# LPCB225_-_DISCHARGE.net
KiCad netlist of a schematic drawn in Altium Designer
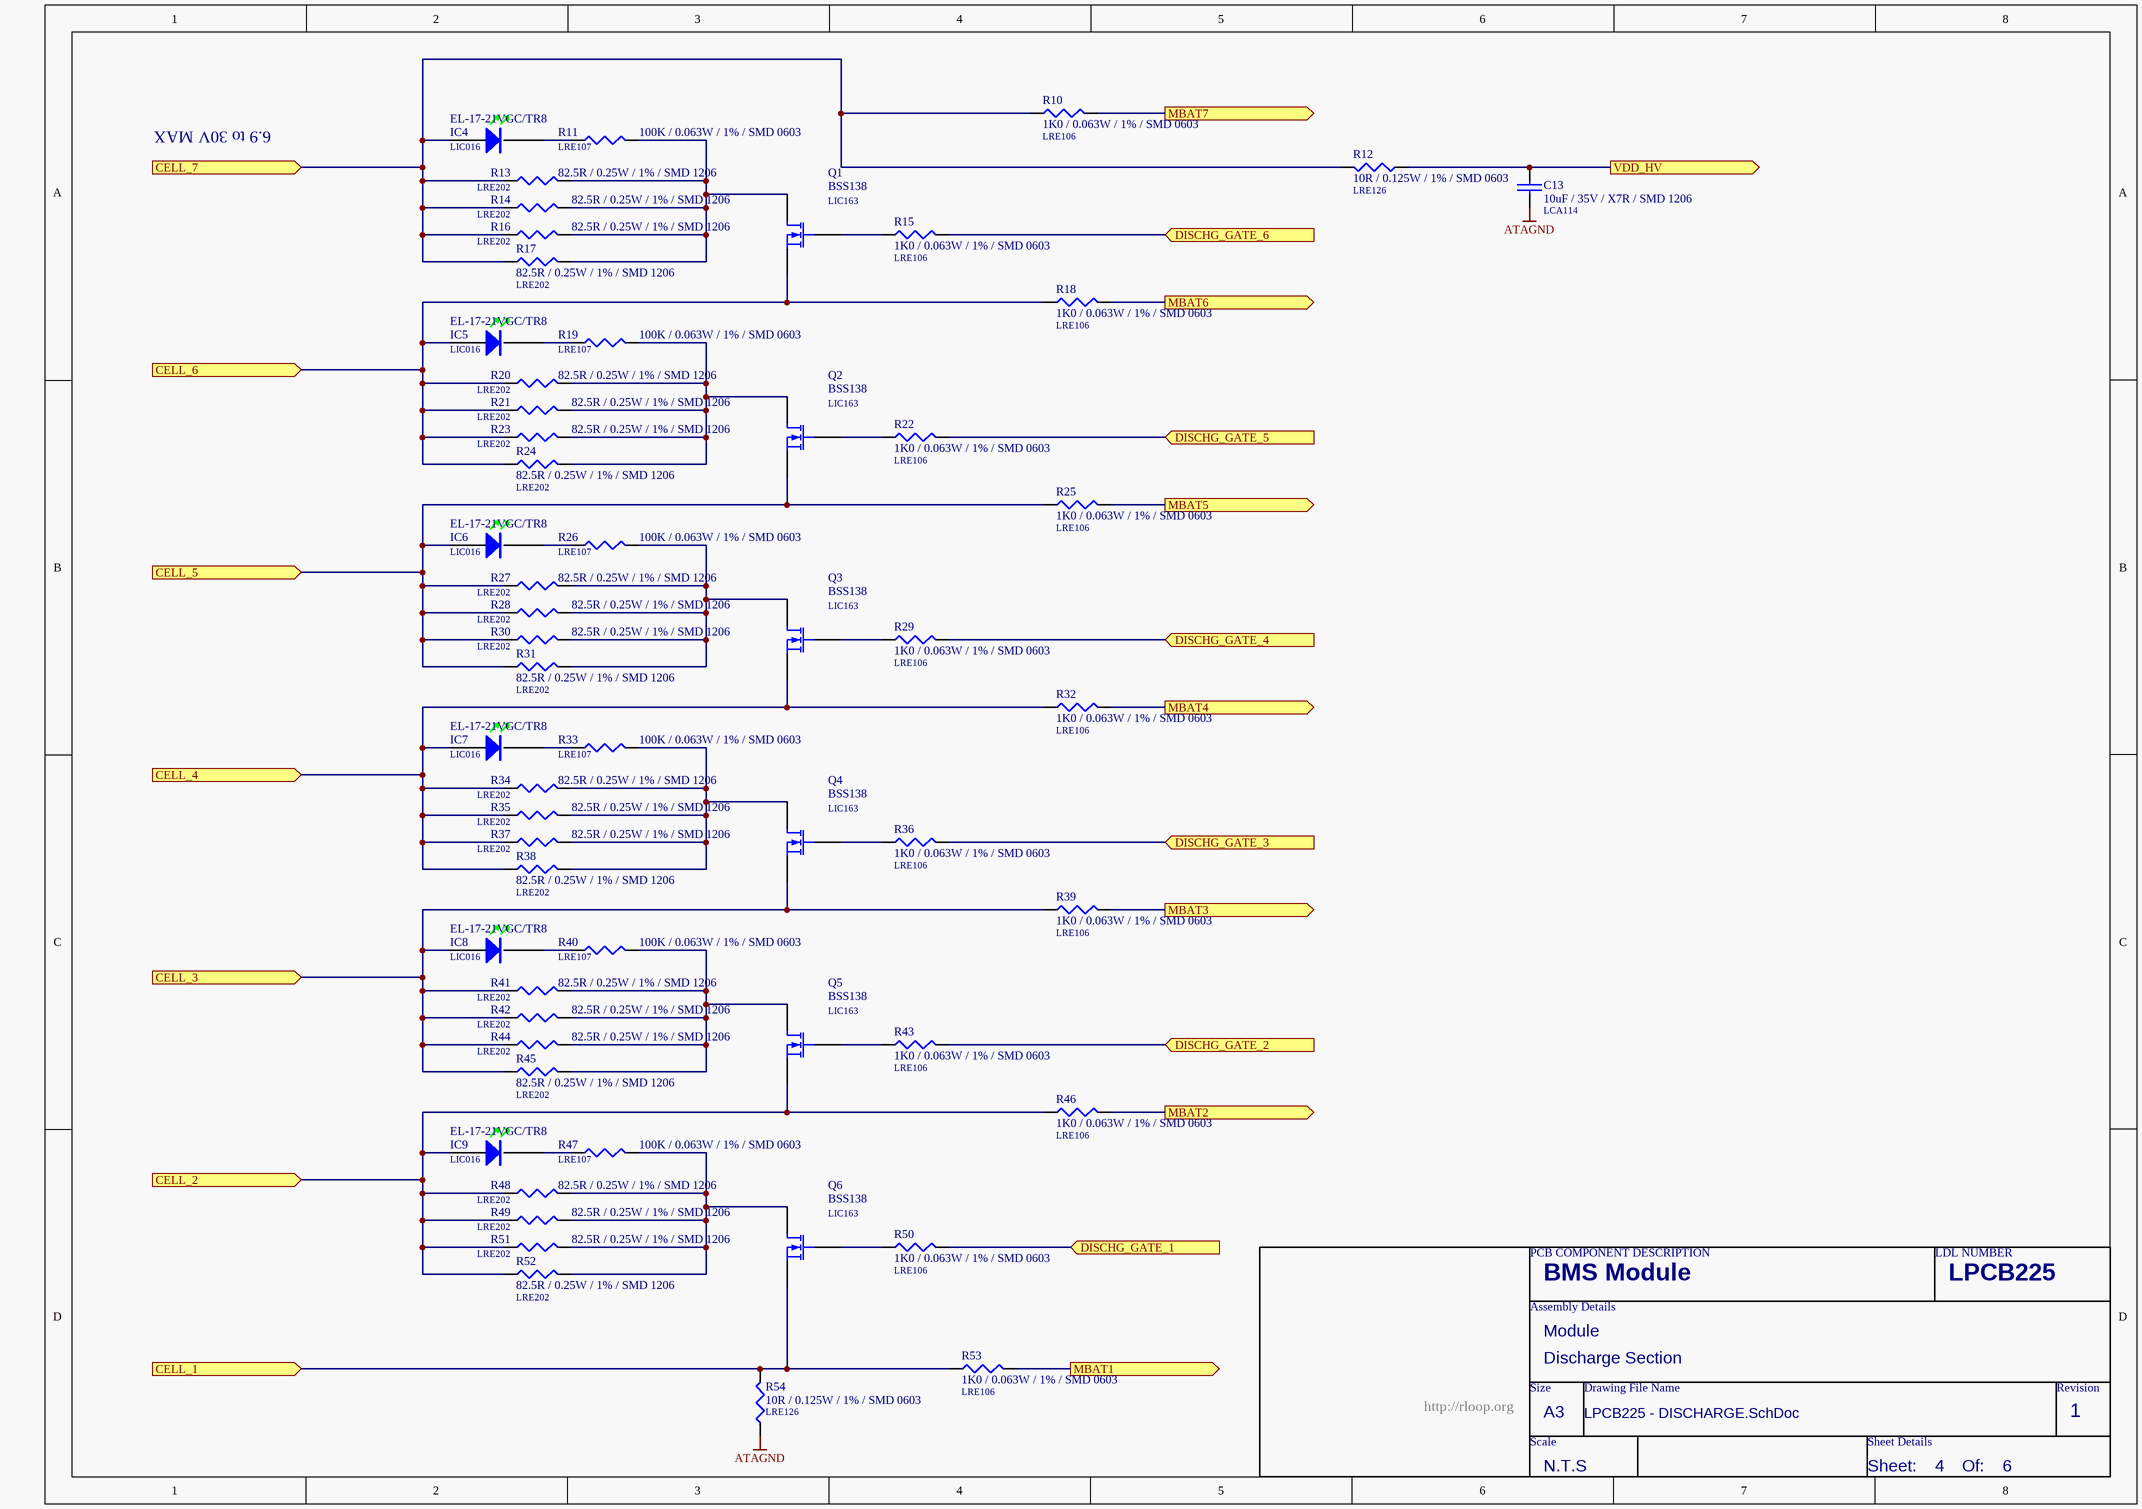
[diagram p0: LPCB225 - DISCHARGE.SchDoc]

(export (version "E")
  (design (tool "Eeschema 10.0.6"))
  (components
    (comp (ref "C13")
      (value "10uF / 35V / X7R / SMD 1206")
      (footprint "LFP043__CC3216-1206")
      (description "Capactor, Ceramic Chip, 10uF, 35V, 20% (X7R), SMD 1206 [LCA114]")
      (fields (field (name "LDL_NUMBER") "LCA114"))
      (libsource (lib "LDL_Capacitors") (part "10uF / 35V / X7R / SMD 1206"))
    )
    (comp (ref "IC4")
      (value "EL-17-21VGC/TR8")
      (footprint "CR2012-0805-LED")
      (description "LED, SMD, 0805 Green [LIC016]")
      (fields (field (name "LDL_NUMBER") "LIC016"))
      (libsource (lib "LDL_Semiconductors") (part "EL-17-21VGC/TR8"))
    )
    (comp (ref "IC5")
      (value "EL-17-21VGC/TR8")
      (footprint "CR2012-0805-LED")
      (description "LED, SMD, 0805 Green [LIC016]")
      (fields (field (name "LDL_NUMBER") "LIC016"))
      (libsource (lib "LDL_Semiconductors") (part "EL-17-21VGC/TR8"))
    )
    (comp (ref "IC6")
      (value "EL-17-21VGC/TR8")
      (footprint "CR2012-0805-LED")
      (description "LED, SMD, 0805 Green [LIC016]")
      (fields (field (name "LDL_NUMBER") "LIC016"))
      (libsource (lib "LDL_Semiconductors") (part "EL-17-21VGC/TR8"))
    )
    (comp (ref "IC7")
      (value "EL-17-21VGC/TR8")
      (footprint "CR2012-0805-LED")
      (description "LED, SMD, 0805 Green [LIC016]")
      (fields (field (name "LDL_NUMBER") "LIC016"))
      (libsource (lib "LDL_Semiconductors") (part "EL-17-21VGC/TR8"))
    )
    (comp (ref "IC8")
      (value "EL-17-21VGC/TR8")
      (footprint "CR2012-0805-LED")
      (description "LED, SMD, 0805 Green [LIC016]")
      (fields (field (name "LDL_NUMBER") "LIC016"))
      (libsource (lib "LDL_Semiconductors") (part "EL-17-21VGC/TR8"))
    )
    (comp (ref "IC9")
      (value "EL-17-21VGC/TR8")
      (footprint "CR2012-0805-LED")
      (description "LED, SMD, 0805 Green [LIC016]")
      (fields (field (name "LDL_NUMBER") "LIC016"))
      (libsource (lib "LDL_Semiconductors") (part "EL-17-21VGC/TR8"))
    )
    (comp (ref "Q1")
      (value "BSS138")
      (footprint "LFP021__SOT23")
      (description "FET, N Channel, Logic Level, SMD SOT23 [LIC163]")
      (fields (field (name "LDL_NUMBER") "LIC163"))
      (libsource (lib "LDL_Semiconductors") (part "BSS138"))
    )
    (comp (ref "Q2")
      (value "BSS138")
      (footprint "LFP021__SOT23")
      (description "FET, N Channel, Logic Level, SMD SOT23 [LIC163]")
      (fields (field (name "LDL_NUMBER") "LIC163"))
      (libsource (lib "LDL_Semiconductors") (part "BSS138"))
    )
    (comp (ref "Q3")
      (value "BSS138")
      (footprint "LFP021__SOT23")
      (description "FET, N Channel, Logic Level, SMD SOT23 [LIC163]")
      (fields (field (name "LDL_NUMBER") "LIC163"))
      (libsource (lib "LDL_Semiconductors") (part "BSS138"))
    )
    (comp (ref "Q4")
      (value "BSS138")
      (footprint "LFP021__SOT23")
      (description "FET, N Channel, Logic Level, SMD SOT23 [LIC163]")
      (fields (field (name "LDL_NUMBER") "LIC163"))
      (libsource (lib "LDL_Semiconductors") (part "BSS138"))
    )
    (comp (ref "Q5")
      (value "BSS138")
      (footprint "LFP021__SOT23")
      (description "FET, N Channel, Logic Level, SMD SOT23 [LIC163]")
      (fields (field (name "LDL_NUMBER") "LIC163"))
      (libsource (lib "LDL_Semiconductors") (part "BSS138"))
    )
    (comp (ref "Q6")
      (value "BSS138")
      (footprint "LFP021__SOT23")
      (description "FET, N Channel, Logic Level, SMD SOT23 [LIC163]")
      (fields (field (name "LDL_NUMBER") "LIC163"))
      (libsource (lib "LDL_Semiconductors") (part "BSS138"))
    )
    (comp (ref "R10")
      (value "1K0 / 0.063W / 1% / SMD 0603")
      (footprint "LFP020__CR1608-0603-IPC7351_B")
      (description "Resistor, Ceramic Chip, 1K0, 0.063W, 1%, SMD 0603 [LRE106]")
      (fields (field (name "LDL_NUMBER") "LRE106"))
      (libsource (lib "LDL_Resistors") (part "1K0 / 0.063W / 1% / SMD 0603"))
    )
    (comp (ref "R11")
      (value "100K / 0.063W / 1% / SMD 0603")
      (footprint "LFP020__CR1608-0603-IPC7351_B")
      (description "Resistor, Ceramic Chip, 100K0, 0.063W, 1%, SMD 0603 [LRE107]")
      (fields (field (name "LDL_NUMBER") "LRE107"))
      (libsource (lib "LDL_Resistors") (part "100K / 0.063W / 1% / SMD 0603"))
    )
    (comp (ref "R12")
      (value "10R / 0.125W / 1% / SMD 0603")
      (footprint "LFP020__CR1608-0603-IPC7351_B")
      (description "Resistor, Ceramic Chip, 10R, 0.063W, 1%, SMD 0603 [LRE126]")
      (fields (field (name "LDL_NUMBER") "LRE126"))
      (libsource (lib "LDL_Resistors") (part "10R / 0.125W / 1% / SMD 0603"))
    )
    (comp (ref "R13")
      (value "82.5R / 0.25W / 1% / SMD 1206")
      (footprint "LFP107__CR3216-1206")
      (description "Resistor, Ceramic Chip, 82.5R, 0.25W, 1%, SMD 1206 [LRE202]")
      (fields (field (name "LDL_NUMBER") "LRE202"))
      (libsource (lib "LDL_Resistors") (part "82.5R / 0.25W / 1% / SMD 1206"))
    )
    (comp (ref "R14")
      (value "82.5R / 0.25W / 1% / SMD 1206")
      (footprint "LFP107__CR3216-1206")
      (description "Resistor, Ceramic Chip, 82.5R, 0.25W, 1%, SMD 1206 [LRE202]")
      (fields (field (name "LDL_NUMBER") "LRE202"))
      (libsource (lib "LDL_Resistors") (part "82.5R / 0.25W / 1% / SMD 1206"))
    )
    (comp (ref "R15")
      (value "1K0 / 0.063W / 1% / SMD 0603")
      (footprint "LFP020__CR1608-0603-IPC7351_B")
      (description "Resistor, Ceramic Chip, 1K0, 0.063W, 1%, SMD 0603 [LRE106]")
      (fields (field (name "LDL_NUMBER") "LRE106"))
      (libsource (lib "LDL_Resistors") (part "1K0 / 0.063W / 1% / SMD 0603"))
    )
    (comp (ref "R16")
      (value "82.5R / 0.25W / 1% / SMD 1206")
      (footprint "LFP107__CR3216-1206")
      (description "Resistor, Ceramic Chip, 82.5R, 0.25W, 1%, SMD 1206 [LRE202]")
      (fields (field (name "LDL_NUMBER") "LRE202"))
      (libsource (lib "LDL_Resistors") (part "82.5R / 0.25W / 1% / SMD 1206"))
    )
    (comp (ref "R17")
      (value "82.5R / 0.25W / 1% / SMD 1206")
      (footprint "LFP107__CR3216-1206")
      (description "Resistor, Ceramic Chip, 82.5R, 0.25W, 1%, SMD 1206 [LRE202]")
      (fields (field (name "LDL_NUMBER") "LRE202"))
      (libsource (lib "LDL_Resistors") (part "82.5R / 0.25W / 1% / SMD 1206"))
    )
    (comp (ref "R18")
      (value "1K0 / 0.063W / 1% / SMD 0603")
      (footprint "LFP020__CR1608-0603-IPC7351_B")
      (description "Resistor, Ceramic Chip, 1K0, 0.063W, 1%, SMD 0603 [LRE106]")
      (fields (field (name "LDL_NUMBER") "LRE106"))
      (libsource (lib "LDL_Resistors") (part "1K0 / 0.063W / 1% / SMD 0603"))
    )
    (comp (ref "R19")
      (value "100K / 0.063W / 1% / SMD 0603")
      (footprint "LFP020__CR1608-0603-IPC7351_B")
      (description "Resistor, Ceramic Chip, 100K0, 0.063W, 1%, SMD 0603 [LRE107]")
      (fields (field (name "LDL_NUMBER") "LRE107"))
      (libsource (lib "LDL_Resistors") (part "100K / 0.063W / 1% / SMD 0603"))
    )
    (comp (ref "R20")
      (value "82.5R / 0.25W / 1% / SMD 1206")
      (footprint "LFP107__CR3216-1206")
      (description "Resistor, Ceramic Chip, 82.5R, 0.25W, 1%, SMD 1206 [LRE202]")
      (fields (field (name "LDL_NUMBER") "LRE202"))
      (libsource (lib "LDL_Resistors") (part "82.5R / 0.25W / 1% / SMD 1206"))
    )
    (comp (ref "R21")
      (value "82.5R / 0.25W / 1% / SMD 1206")
      (footprint "LFP107__CR3216-1206")
      (description "Resistor, Ceramic Chip, 82.5R, 0.25W, 1%, SMD 1206 [LRE202]")
      (fields (field (name "LDL_NUMBER") "LRE202"))
      (libsource (lib "LDL_Resistors") (part "82.5R / 0.25W / 1% / SMD 1206"))
    )
    (comp (ref "R22")
      (value "1K0 / 0.063W / 1% / SMD 0603")
      (footprint "LFP020__CR1608-0603-IPC7351_B")
      (description "Resistor, Ceramic Chip, 1K0, 0.063W, 1%, SMD 0603 [LRE106]")
      (fields (field (name "LDL_NUMBER") "LRE106"))
      (libsource (lib "LDL_Resistors") (part "1K0 / 0.063W / 1% / SMD 0603"))
    )
    (comp (ref "R23")
      (value "82.5R / 0.25W / 1% / SMD 1206")
      (footprint "LFP107__CR3216-1206")
      (description "Resistor, Ceramic Chip, 82.5R, 0.25W, 1%, SMD 1206 [LRE202]")
      (fields (field (name "LDL_NUMBER") "LRE202"))
      (libsource (lib "LDL_Resistors") (part "82.5R / 0.25W / 1% / SMD 1206"))
    )
    (comp (ref "R24")
      (value "82.5R / 0.25W / 1% / SMD 1206")
      (footprint "LFP107__CR3216-1206")
      (description "Resistor, Ceramic Chip, 82.5R, 0.25W, 1%, SMD 1206 [LRE202]")
      (fields (field (name "LDL_NUMBER") "LRE202"))
      (libsource (lib "LDL_Resistors") (part "82.5R / 0.25W / 1% / SMD 1206"))
    )
    (comp (ref "R25")
      (value "1K0 / 0.063W / 1% / SMD 0603")
      (footprint "LFP020__CR1608-0603-IPC7351_B")
      (description "Resistor, Ceramic Chip, 1K0, 0.063W, 1%, SMD 0603 [LRE106]")
      (fields (field (name "LDL_NUMBER") "LRE106"))
      (libsource (lib "LDL_Resistors") (part "1K0 / 0.063W / 1% / SMD 0603"))
    )
    (comp (ref "R26")
      (value "100K / 0.063W / 1% / SMD 0603")
      (footprint "LFP020__CR1608-0603-IPC7351_B")
      (description "Resistor, Ceramic Chip, 100K0, 0.063W, 1%, SMD 0603 [LRE107]")
      (fields (field (name "LDL_NUMBER") "LRE107"))
      (libsource (lib "LDL_Resistors") (part "100K / 0.063W / 1% / SMD 0603"))
    )
    (comp (ref "R27")
      (value "82.5R / 0.25W / 1% / SMD 1206")
      (footprint "LFP107__CR3216-1206")
      (description "Resistor, Ceramic Chip, 82.5R, 0.25W, 1%, SMD 1206 [LRE202]")
      (fields (field (name "LDL_NUMBER") "LRE202"))
      (libsource (lib "LDL_Resistors") (part "82.5R / 0.25W / 1% / SMD 1206"))
    )
    (comp (ref "R28")
      (value "82.5R / 0.25W / 1% / SMD 1206")
      (footprint "LFP107__CR3216-1206")
      (description "Resistor, Ceramic Chip, 82.5R, 0.25W, 1%, SMD 1206 [LRE202]")
      (fields (field (name "LDL_NUMBER") "LRE202"))
      (libsource (lib "LDL_Resistors") (part "82.5R / 0.25W / 1% / SMD 1206"))
    )
    (comp (ref "R29")
      (value "1K0 / 0.063W / 1% / SMD 0603")
      (footprint "LFP020__CR1608-0603-IPC7351_B")
      (description "Resistor, Ceramic Chip, 1K0, 0.063W, 1%, SMD 0603 [LRE106]")
      (fields (field (name "LDL_NUMBER") "LRE106"))
      (libsource (lib "LDL_Resistors") (part "1K0 / 0.063W / 1% / SMD 0603"))
    )
    (comp (ref "R30")
      (value "82.5R / 0.25W / 1% / SMD 1206")
      (footprint "LFP107__CR3216-1206")
      (description "Resistor, Ceramic Chip, 82.5R, 0.25W, 1%, SMD 1206 [LRE202]")
      (fields (field (name "LDL_NUMBER") "LRE202"))
      (libsource (lib "LDL_Resistors") (part "82.5R / 0.25W / 1% / SMD 1206"))
    )
    (comp (ref "R31")
      (value "82.5R / 0.25W / 1% / SMD 1206")
      (footprint "LFP107__CR3216-1206")
      (description "Resistor, Ceramic Chip, 82.5R, 0.25W, 1%, SMD 1206 [LRE202]")
      (fields (field (name "LDL_NUMBER") "LRE202"))
      (libsource (lib "LDL_Resistors") (part "82.5R / 0.25W / 1% / SMD 1206"))
    )
    (comp (ref "R32")
      (value "1K0 / 0.063W / 1% / SMD 0603")
      (footprint "LFP020__CR1608-0603-IPC7351_B")
      (description "Resistor, Ceramic Chip, 1K0, 0.063W, 1%, SMD 0603 [LRE106]")
      (fields (field (name "LDL_NUMBER") "LRE106"))
      (libsource (lib "LDL_Resistors") (part "1K0 / 0.063W / 1% / SMD 0603"))
    )
    (comp (ref "R33")
      (value "100K / 0.063W / 1% / SMD 0603")
      (footprint "LFP020__CR1608-0603-IPC7351_B")
      (description "Resistor, Ceramic Chip, 100K0, 0.063W, 1%, SMD 0603 [LRE107]")
      (fields (field (name "LDL_NUMBER") "LRE107"))
      (libsource (lib "LDL_Resistors") (part "100K / 0.063W / 1% / SMD 0603"))
    )
    (comp (ref "R34")
      (value "82.5R / 0.25W / 1% / SMD 1206")
      (footprint "LFP107__CR3216-1206")
      (description "Resistor, Ceramic Chip, 82.5R, 0.25W, 1%, SMD 1206 [LRE202]")
      (fields (field (name "LDL_NUMBER") "LRE202"))
      (libsource (lib "LDL_Resistors") (part "82.5R / 0.25W / 1% / SMD 1206"))
    )
    (comp (ref "R35")
      (value "82.5R / 0.25W / 1% / SMD 1206")
      (footprint "LFP107__CR3216-1206")
      (description "Resistor, Ceramic Chip, 82.5R, 0.25W, 1%, SMD 1206 [LRE202]")
      (fields (field (name "LDL_NUMBER") "LRE202"))
      (libsource (lib "LDL_Resistors") (part "82.5R / 0.25W / 1% / SMD 1206"))
    )
    (comp (ref "R36")
      (value "1K0 / 0.063W / 1% / SMD 0603")
      (footprint "LFP020__CR1608-0603-IPC7351_B")
      (description "Resistor, Ceramic Chip, 1K0, 0.063W, 1%, SMD 0603 [LRE106]")
      (fields (field (name "LDL_NUMBER") "LRE106"))
      (libsource (lib "LDL_Resistors") (part "1K0 / 0.063W / 1% / SMD 0603"))
    )
    (comp (ref "R37")
      (value "82.5R / 0.25W / 1% / SMD 1206")
      (footprint "LFP107__CR3216-1206")
      (description "Resistor, Ceramic Chip, 82.5R, 0.25W, 1%, SMD 1206 [LRE202]")
      (fields (field (name "LDL_NUMBER") "LRE202"))
      (libsource (lib "LDL_Resistors") (part "82.5R / 0.25W / 1% / SMD 1206"))
    )
    (comp (ref "R38")
      (value "82.5R / 0.25W / 1% / SMD 1206")
      (footprint "LFP107__CR3216-1206")
      (description "Resistor, Ceramic Chip, 82.5R, 0.25W, 1%, SMD 1206 [LRE202]")
      (fields (field (name "LDL_NUMBER") "LRE202"))
      (libsource (lib "LDL_Resistors") (part "82.5R / 0.25W / 1% / SMD 1206"))
    )
    (comp (ref "R39")
      (value "1K0 / 0.063W / 1% / SMD 0603")
      (footprint "LFP020__CR1608-0603-IPC7351_B")
      (description "Resistor, Ceramic Chip, 1K0, 0.063W, 1%, SMD 0603 [LRE106]")
      (fields (field (name "LDL_NUMBER") "LRE106"))
      (libsource (lib "LDL_Resistors") (part "1K0 / 0.063W / 1% / SMD 0603"))
    )
    (comp (ref "R40")
      (value "100K / 0.063W / 1% / SMD 0603")
      (footprint "LFP020__CR1608-0603-IPC7351_B")
      (description "Resistor, Ceramic Chip, 100K0, 0.063W, 1%, SMD 0603 [LRE107]")
      (fields (field (name "LDL_NUMBER") "LRE107"))
      (libsource (lib "LDL_Resistors") (part "100K / 0.063W / 1% / SMD 0603"))
    )
    (comp (ref "R41")
      (value "82.5R / 0.25W / 1% / SMD 1206")
      (footprint "LFP107__CR3216-1206")
      (description "Resistor, Ceramic Chip, 82.5R, 0.25W, 1%, SMD 1206 [LRE202]")
      (fields (field (name "LDL_NUMBER") "LRE202"))
      (libsource (lib "LDL_Resistors") (part "82.5R / 0.25W / 1% / SMD 1206"))
    )
    (comp (ref "R42")
      (value "82.5R / 0.25W / 1% / SMD 1206")
      (footprint "LFP107__CR3216-1206")
      (description "Resistor, Ceramic Chip, 82.5R, 0.25W, 1%, SMD 1206 [LRE202]")
      (fields (field (name "LDL_NUMBER") "LRE202"))
      (libsource (lib "LDL_Resistors") (part "82.5R / 0.25W / 1% / SMD 1206"))
    )
    (comp (ref "R43")
      (value "1K0 / 0.063W / 1% / SMD 0603")
      (footprint "LFP020__CR1608-0603-IPC7351_B")
      (description "Resistor, Ceramic Chip, 1K0, 0.063W, 1%, SMD 0603 [LRE106]")
      (fields (field (name "LDL_NUMBER") "LRE106"))
      (libsource (lib "LDL_Resistors") (part "1K0 / 0.063W / 1% / SMD 0603"))
    )
    (comp (ref "R44")
      (value "82.5R / 0.25W / 1% / SMD 1206")
      (footprint "LFP107__CR3216-1206")
      (description "Resistor, Ceramic Chip, 82.5R, 0.25W, 1%, SMD 1206 [LRE202]")
      (fields (field (name "LDL_NUMBER") "LRE202"))
      (libsource (lib "LDL_Resistors") (part "82.5R / 0.25W / 1% / SMD 1206"))
    )
    (comp (ref "R45")
      (value "82.5R / 0.25W / 1% / SMD 1206")
      (footprint "LFP107__CR3216-1206")
      (description "Resistor, Ceramic Chip, 82.5R, 0.25W, 1%, SMD 1206 [LRE202]")
      (fields (field (name "LDL_NUMBER") "LRE202"))
      (libsource (lib "LDL_Resistors") (part "82.5R / 0.25W / 1% / SMD 1206"))
    )
    (comp (ref "R46")
      (value "1K0 / 0.063W / 1% / SMD 0603")
      (footprint "LFP020__CR1608-0603-IPC7351_B")
      (description "Resistor, Ceramic Chip, 1K0, 0.063W, 1%, SMD 0603 [LRE106]")
      (fields (field (name "LDL_NUMBER") "LRE106"))
      (libsource (lib "LDL_Resistors") (part "1K0 / 0.063W / 1% / SMD 0603"))
    )
    (comp (ref "R47")
      (value "100K / 0.063W / 1% / SMD 0603")
      (footprint "LFP020__CR1608-0603-IPC7351_B")
      (description "Resistor, Ceramic Chip, 100K0, 0.063W, 1%, SMD 0603 [LRE107]")
      (fields (field (name "LDL_NUMBER") "LRE107"))
      (libsource (lib "LDL_Resistors") (part "100K / 0.063W / 1% / SMD 0603"))
    )
    (comp (ref "R48")
      (value "82.5R / 0.25W / 1% / SMD 1206")
      (footprint "LFP107__CR3216-1206")
      (description "Resistor, Ceramic Chip, 82.5R, 0.25W, 1%, SMD 1206 [LRE202]")
      (fields (field (name "LDL_NUMBER") "LRE202"))
      (libsource (lib "LDL_Resistors") (part "82.5R / 0.25W / 1% / SMD 1206"))
    )
    (comp (ref "R49")
      (value "82.5R / 0.25W / 1% / SMD 1206")
      (footprint "LFP107__CR3216-1206")
      (description "Resistor, Ceramic Chip, 82.5R, 0.25W, 1%, SMD 1206 [LRE202]")
      (fields (field (name "LDL_NUMBER") "LRE202"))
      (libsource (lib "LDL_Resistors") (part "82.5R / 0.25W / 1% / SMD 1206"))
    )
    (comp (ref "R50")
      (value "1K0 / 0.063W / 1% / SMD 0603")
      (footprint "LFP020__CR1608-0603-IPC7351_B")
      (description "Resistor, Ceramic Chip, 1K0, 0.063W, 1%, SMD 0603 [LRE106]")
      (fields (field (name "LDL_NUMBER") "LRE106"))
      (libsource (lib "LDL_Resistors") (part "1K0 / 0.063W / 1% / SMD 0603"))
    )
    (comp (ref "R51")
      (value "82.5R / 0.25W / 1% / SMD 1206")
      (footprint "LFP107__CR3216-1206")
      (description "Resistor, Ceramic Chip, 82.5R, 0.25W, 1%, SMD 1206 [LRE202]")
      (fields (field (name "LDL_NUMBER") "LRE202"))
      (libsource (lib "LDL_Resistors") (part "82.5R / 0.25W / 1% / SMD 1206"))
    )
    (comp (ref "R52")
      (value "82.5R / 0.25W / 1% / SMD 1206")
      (footprint "LFP107__CR3216-1206")
      (description "Resistor, Ceramic Chip, 82.5R, 0.25W, 1%, SMD 1206 [LRE202]")
      (fields (field (name "LDL_NUMBER") "LRE202"))
      (libsource (lib "LDL_Resistors") (part "82.5R / 0.25W / 1% / SMD 1206"))
    )
    (comp (ref "R53")
      (value "1K0 / 0.063W / 1% / SMD 0603")
      (footprint "LFP020__CR1608-0603-IPC7351_B")
      (description "Resistor, Ceramic Chip, 1K0, 0.063W, 1%, SMD 0603 [LRE106]")
      (fields (field (name "LDL_NUMBER") "LRE106"))
      (libsource (lib "LDL_Resistors") (part "1K0 / 0.063W / 1% / SMD 0603"))
    )
    (comp (ref "R54")
      (value "10R / 0.125W / 1% / SMD 0603")
      (footprint "LFP020__CR1608-0603-IPC7351_B")
      (description "Resistor, Ceramic Chip, 10R, 0.063W, 1%, SMD 0603 [LRE126]")
      (fields (field (name "LDL_NUMBER") "LRE126"))
      (libsource (lib "LDL_Resistors") (part "10R / 0.125W / 1% / SMD 0603"))
    )
  )
  (nets
    (net (code "1") (name "/CELL_1") (class "Default")
      (node (ref "Q6") (pin "2") (pinfunction "S_2") (pintype "passive"))
      (node (ref "R53") (pin "1") (pintype "passive"))
      (node (ref "R54") (pin "2") (pintype "passive"))
    )
    (net (code "2") (name "/CELL_2") (class "Default")
      (node (ref "IC9") (pin "A") (pintype "passive"))
      (node (ref "Q5") (pin "2") (pinfunction "S_2") (pintype "passive"))
      (node (ref "R46") (pin "1") (pintype "passive"))
      (node (ref "R48") (pin "1") (pintype "passive"))
      (node (ref "R49") (pin "1") (pintype "passive"))
      (node (ref "R51") (pin "1") (pintype "passive"))
      (node (ref "R52") (pin "1") (pintype "passive"))
    )
    (net (code "3") (name "/CELL_3") (class "Default")
      (node (ref "IC8") (pin "A") (pintype "passive"))
      (node (ref "Q4") (pin "2") (pinfunction "S_2") (pintype "passive"))
      (node (ref "R39") (pin "1") (pintype "passive"))
      (node (ref "R41") (pin "1") (pintype "passive"))
      (node (ref "R42") (pin "1") (pintype "passive"))
      (node (ref "R44") (pin "1") (pintype "passive"))
      (node (ref "R45") (pin "1") (pintype "passive"))
    )
    (net (code "4") (name "/CELL_4") (class "Default")
      (node (ref "IC7") (pin "A") (pintype "passive"))
      (node (ref "Q3") (pin "2") (pinfunction "S_2") (pintype "passive"))
      (node (ref "R32") (pin "1") (pintype "passive"))
      (node (ref "R34") (pin "1") (pintype "passive"))
      (node (ref "R35") (pin "1") (pintype "passive"))
      (node (ref "R37") (pin "1") (pintype "passive"))
      (node (ref "R38") (pin "1") (pintype "passive"))
    )
    (net (code "5") (name "/CELL_5") (class "Default")
      (node (ref "IC6") (pin "A") (pintype "passive"))
      (node (ref "Q2") (pin "2") (pinfunction "S_2") (pintype "passive"))
      (node (ref "R25") (pin "1") (pintype "passive"))
      (node (ref "R27") (pin "1") (pintype "passive"))
      (node (ref "R28") (pin "1") (pintype "passive"))
      (node (ref "R30") (pin "1") (pintype "passive"))
      (node (ref "R31") (pin "1") (pintype "passive"))
    )
    (net (code "6") (name "/CELL_6") (class "Default")
      (node (ref "IC5") (pin "A") (pintype "passive"))
      (node (ref "Q1") (pin "2") (pinfunction "S_2") (pintype "passive"))
      (node (ref "R18") (pin "1") (pintype "passive"))
      (node (ref "R20") (pin "1") (pintype "passive"))
      (node (ref "R21") (pin "1") (pintype "passive"))
      (node (ref "R23") (pin "1") (pintype "passive"))
      (node (ref "R24") (pin "1") (pintype "passive"))
    )
    (net (code "7") (name "/CELL_7") (class "Default")
      (node (ref "IC4") (pin "A") (pintype "passive"))
      (node (ref "R10") (pin "1") (pintype "passive"))
      (node (ref "R12") (pin "2") (pintype "passive"))
      (node (ref "R13") (pin "1") (pintype "passive"))
      (node (ref "R14") (pin "1") (pintype "passive"))
      (node (ref "R16") (pin "1") (pintype "passive"))
      (node (ref "R17") (pin "1") (pintype "passive"))
    )
    (net (code "8") (name "/DISCHG_GATE_1") (class "Default")
      (node (ref "R50") (pin "2") (pintype "passive"))
    )
    (net (code "9") (name "/DISCHG_GATE_2") (class "Default")
      (node (ref "R43") (pin "2") (pintype "passive"))
    )
    (net (code "10") (name "/DISCHG_GATE_3") (class "Default")
      (node (ref "R36") (pin "2") (pintype "passive"))
    )
    (net (code "11") (name "/DISCHG_GATE_4") (class "Default")
      (node (ref "R29") (pin "2") (pintype "passive"))
    )
    (net (code "12") (name "/DISCHG_GATE_5") (class "Default")
      (node (ref "R22") (pin "2") (pintype "passive"))
    )
    (net (code "13") (name "/DISCHG_GATE_6") (class "Default")
      (node (ref "R15") (pin "2") (pintype "passive"))
    )
    (net (code "14") (name "/MBAT1") (class "Default") (node (ref "R53") (pin "2") (pintype "passive")))
    (net (code "15") (name "/MBAT2") (class "Default") (node (ref "R46") (pin "2") (pintype "passive")))
    (net (code "16") (name "/MBAT3") (class "Default") (node (ref "R39") (pin "2") (pintype "passive")))
    (net (code "17") (name "/MBAT4") (class "Default") (node (ref "R32") (pin "2") (pintype "passive")))
    (net (code "18") (name "/MBAT5") (class "Default") (node (ref "R25") (pin "2") (pintype "passive")))
    (net (code "19") (name "/MBAT6") (class "Default") (node (ref "R18") (pin "2") (pintype "passive")))
    (net (code "20") (name "/MBAT7") (class "Default") (node (ref "R10") (pin "2") (pintype "passive")))
    (net (code "21") (name "/VDD_HV") (class "Default")
      (node (ref "C13") (pin "1") (pintype "passive"))
      (node (ref "R12") (pin "1") (pintype "passive"))
    )
    (net (code "22") (name "ATAGND") (class "Default")
      (node (ref "C13") (pin "2") (pintype "passive"))
      (node (ref "R54") (pin "1") (pintype "passive"))
    )
    (net (code "23") (name "Net-(IC4-PadK)") (class "Default")
      (node (ref "IC4") (pin "K") (pintype "passive"))
      (node (ref "R11") (pin "1") (pintype "passive"))
    )
    (net (code "24") (name "Net-(IC5-PadK)") (class "Default")
      (node (ref "IC5") (pin "K") (pintype "passive"))
      (node (ref "R19") (pin "1") (pintype "passive"))
    )
    (net (code "25") (name "Net-(IC6-PadK)") (class "Default")
      (node (ref "IC6") (pin "K") (pintype "passive"))
      (node (ref "R26") (pin "1") (pintype "passive"))
    )
    (net (code "26") (name "Net-(IC7-PadK)") (class "Default")
      (node (ref "IC7") (pin "K") (pintype "passive"))
      (node (ref "R33") (pin "1") (pintype "passive"))
    )
    (net (code "27") (name "Net-(IC8-PadK)") (class "Default")
      (node (ref "IC8") (pin "K") (pintype "passive"))
      (node (ref "R40") (pin "1") (pintype "passive"))
    )
    (net (code "28") (name "Net-(IC9-PadK)") (class "Default")
      (node (ref "IC9") (pin "K") (pintype "passive"))
      (node (ref "R47") (pin "1") (pintype "passive"))
    )
    (net (code "29") (name "Net-(Q1-D)") (class "Default")
      (node (ref "Q1") (pin "3") (pinfunction "D_3") (pintype "passive"))
      (node (ref "R11") (pin "2") (pintype "passive"))
      (node (ref "R13") (pin "2") (pintype "passive"))
      (node (ref "R14") (pin "2") (pintype "passive"))
      (node (ref "R16") (pin "2") (pintype "passive"))
      (node (ref "R17") (pin "2") (pintype "passive"))
    )
    (net (code "30") (name "Net-(Q1-G)") (class "Default")
      (node (ref "Q1") (pin "1") (pinfunction "G_1") (pintype "passive"))
      (node (ref "R15") (pin "1") (pintype "passive"))
    )
    (net (code "31") (name "Net-(Q2-D)") (class "Default")
      (node (ref "Q2") (pin "3") (pinfunction "D_3") (pintype "passive"))
      (node (ref "R19") (pin "2") (pintype "passive"))
      (node (ref "R20") (pin "2") (pintype "passive"))
      (node (ref "R21") (pin "2") (pintype "passive"))
      (node (ref "R23") (pin "2") (pintype "passive"))
      (node (ref "R24") (pin "2") (pintype "passive"))
    )
    (net (code "32") (name "Net-(Q2-G)") (class "Default")
      (node (ref "Q2") (pin "1") (pinfunction "G_1") (pintype "passive"))
      (node (ref "R22") (pin "1") (pintype "passive"))
    )
    (net (code "33") (name "Net-(Q3-D)") (class "Default")
      (node (ref "Q3") (pin "3") (pinfunction "D_3") (pintype "passive"))
      (node (ref "R26") (pin "2") (pintype "passive"))
      (node (ref "R27") (pin "2") (pintype "passive"))
      (node (ref "R28") (pin "2") (pintype "passive"))
      (node (ref "R30") (pin "2") (pintype "passive"))
      (node (ref "R31") (pin "2") (pintype "passive"))
    )
    (net (code "34") (name "Net-(Q3-G)") (class "Default")
      (node (ref "Q3") (pin "1") (pinfunction "G_1") (pintype "passive"))
      (node (ref "R29") (pin "1") (pintype "passive"))
    )
    (net (code "35") (name "Net-(Q4-D)") (class "Default")
      (node (ref "Q4") (pin "3") (pinfunction "D_3") (pintype "passive"))
      (node (ref "R33") (pin "2") (pintype "passive"))
      (node (ref "R34") (pin "2") (pintype "passive"))
      (node (ref "R35") (pin "2") (pintype "passive"))
      (node (ref "R37") (pin "2") (pintype "passive"))
      (node (ref "R38") (pin "2") (pintype "passive"))
    )
    (net (code "36") (name "Net-(Q4-G)") (class "Default")
      (node (ref "Q4") (pin "1") (pinfunction "G_1") (pintype "passive"))
      (node (ref "R36") (pin "1") (pintype "passive"))
    )
    (net (code "37") (name "Net-(Q5-D)") (class "Default")
      (node (ref "Q5") (pin "3") (pinfunction "D_3") (pintype "passive"))
      (node (ref "R40") (pin "2") (pintype "passive"))
      (node (ref "R41") (pin "2") (pintype "passive"))
      (node (ref "R42") (pin "2") (pintype "passive"))
      (node (ref "R44") (pin "2") (pintype "passive"))
      (node (ref "R45") (pin "2") (pintype "passive"))
    )
    (net (code "38") (name "Net-(Q5-G)") (class "Default")
      (node (ref "Q5") (pin "1") (pinfunction "G_1") (pintype "passive"))
      (node (ref "R43") (pin "1") (pintype "passive"))
    )
    (net (code "39") (name "Net-(Q6-D)") (class "Default")
      (node (ref "Q6") (pin "3") (pinfunction "D_3") (pintype "passive"))
      (node (ref "R47") (pin "2") (pintype "passive"))
      (node (ref "R48") (pin "2") (pintype "passive"))
      (node (ref "R49") (pin "2") (pintype "passive"))
      (node (ref "R51") (pin "2") (pintype "passive"))
      (node (ref "R52") (pin "2") (pintype "passive"))
    )
    (net (code "40") (name "Net-(Q6-G)") (class "Default")
      (node (ref "Q6") (pin "1") (pinfunction "G_1") (pintype "passive"))
      (node (ref "R50") (pin "1") (pintype "passive"))
    )
  )
)
